# PidiPad.net
KiCad netlist of a schematic drawn in EAGLE
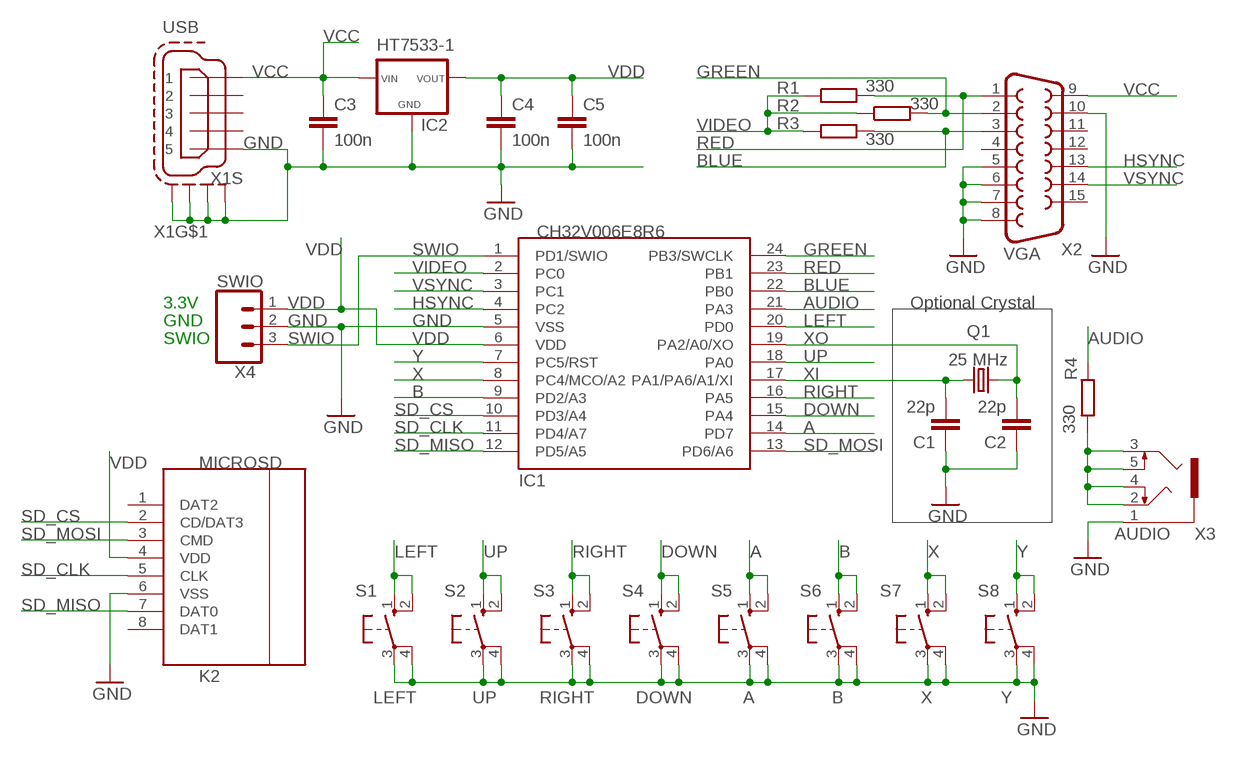
[diagram p0: schematic, sheet 1]

(export (version "E")
  (design (tool "Eeschema 10.0.6"))
  (components
    (comp (ref "C1")
      (value "22p")
      (footprint "eagle-import:C050-024X044")
      (libsource (lib "eagle-import") (part "C-EU050-024X044"))
    )
    (comp (ref "C2")
      (value "22p")
      (footprint "eagle-import:C050-024X044")
      (libsource (lib "eagle-import") (part "C-EU050-024X044"))
    )
    (comp (ref "C3")
      (value "100n")
      (footprint "eagle-import:C050-024X044")
      (libsource (lib "eagle-import") (part "C-EU050-024X044"))
    )
    (comp (ref "C4")
      (value "100n")
      (footprint "eagle-import:C050-024X044")
      (libsource (lib "eagle-import") (part "C-EU050-024X044"))
    )
    (comp (ref "C5")
      (value "100n")
      (footprint "eagle-import:C050-024X044")
      (libsource (lib "eagle-import") (part "C-EU050-024X044"))
    )
    (comp (ref "IC1")
      (value "CH32V006E8R6")
      (footprint "eagle-import:QSOP24")
      (libsource (lib "eagle-import") (part "CH32V006E8R6"))
    )
    (comp (ref "IC2")
      (value "HT7533-1")
      (footprint "eagle-import:HT7533-1")
      (libsource (lib "eagle-import") (part "HT7533-1"))
    )
    (comp (ref "K2")
      (value "MICROSD")
      (footprint "eagle-import:MICROSD")
      (libsource (lib "eagle-import") (part "MICROSD"))
    )
    (comp (ref "Q1")
      (value "25 MHz")
      (footprint "eagle-import:HC49U-V")
      (libsource (lib "eagle-import") (part "CRYSTALHC49U-V"))
    )
    (comp (ref "R1")
      (value "330")
      (footprint "eagle-import:0204_7")
      (libsource (lib "eagle-import") (part "R-EU_0204/7"))
    )
    (comp (ref "R2")
      (value "330")
      (footprint "eagle-import:0204_7")
      (libsource (lib "eagle-import") (part "R-EU_0204/7"))
    )
    (comp (ref "R3")
      (value "330")
      (footprint "eagle-import:0204_7")
      (libsource (lib "eagle-import") (part "R-EU_0204/7"))
    )
    (comp (ref "R4")
      (value "330")
      (footprint "eagle-import:0204_7")
      (libsource (lib "eagle-import") (part "R-EU_0204/7"))
    )
    (comp (ref "S1")
      (value "LEFT")
      (footprint "eagle-import:B3F-10XX")
      (fields (field (name "MPN") "B3F-1000"))
      (libsource (lib "eagle-import") (part "10-XX"))
    )
    (comp (ref "S2")
      (value "UP")
      (footprint "eagle-import:B3F-10XX")
      (fields (field (name "MPN") "B3F-1000"))
      (libsource (lib "eagle-import") (part "10-XX"))
    )
    (comp (ref "S3")
      (value "RIGHT")
      (footprint "eagle-import:B3F-10XX")
      (fields (field (name "MPN") "B3F-1000"))
      (libsource (lib "eagle-import") (part "10-XX"))
    )
    (comp (ref "S4")
      (value "DOWN")
      (footprint "eagle-import:B3F-10XX")
      (fields (field (name "MPN") "B3F-1000"))
      (libsource (lib "eagle-import") (part "10-XX"))
    )
    (comp (ref "S5")
      (value "A")
      (footprint "eagle-import:B3F-10XX")
      (fields (field (name "MPN") "B3F-1000"))
      (libsource (lib "eagle-import") (part "10-XX"))
    )
    (comp (ref "S6")
      (value "B")
      (footprint "eagle-import:B3F-10XX")
      (fields (field (name "MPN") "B3F-1000"))
      (libsource (lib "eagle-import") (part "10-XX"))
    )
    (comp (ref "S7")
      (value "X")
      (footprint "eagle-import:B3F-10XX")
      (fields (field (name "MPN") "B3F-1000"))
      (libsource (lib "eagle-import") (part "10-XX"))
    )
    (comp (ref "S8")
      (value "Y")
      (footprint "eagle-import:B3F-10XX")
      (fields (field (name "MPN") "B3F-1000"))
      (libsource (lib "eagle-import") (part "10-XX"))
    )
    (comp (ref "X1")
      (value "USB")
      (footprint "eagle-import:32005-201")
      (libsource (lib "eagle-import") (part "MINI-USB-SCHIELD-32005-201"))
    )
    (comp (ref "X2")
      (value "VGA")
      (footprint "eagle-import:HDF15H")
      (libsource (lib "eagle-import") (part "F15HDH"))
    )
    (comp (ref "X3")
      (value "AUDIO")
      (footprint "eagle-import:1503_09")
      (libsource (lib "eagle-import") (part "1503_09"))
    )
    (comp (ref "X4")
      (value "SWIO")
      (footprint "eagle-import:1X03")
      (libsource (lib "eagle-import") (part "CONN_03"))
    )
  )
  (nets
    (net (code "1") (name "/A") (class "Default")
      (node (ref "IC1") (pin "14") (pinfunction "PD7_14") (pintype "bidirectional"))
      (node (ref "S5") (pin "1") (pinfunction "S_1") (pintype "passive"))
      (node (ref "S5") (pin "2") (pinfunction "S1_2") (pintype "passive"))
    )
    (net (code "2") (name "/AUDIO") (class "Default")
      (node (ref "IC1") (pin "21") (pinfunction "PA3_21") (pintype "bidirectional"))
      (node (ref "R4") (pin "2") (pinfunction "2_2") (pintype "passive"))
    )
    (net (code "3") (name "/B") (class "Default")
      (node (ref "IC1") (pin "9") (pinfunction "PD2/A3_9") (pintype "bidirectional"))
      (node (ref "S6") (pin "1") (pinfunction "S_1") (pintype "passive"))
      (node (ref "S6") (pin "2") (pinfunction "S1_2") (pintype "passive"))
    )
    (net (code "4") (name "/BLUE") (class "Default")
      (node (ref "IC1") (pin "22") (pinfunction "PB0_22") (pintype "bidirectional"))
      (node (ref "R3") (pin "2") (pinfunction "2_2") (pintype "passive"))
      (node (ref "X2") (pin "3") (pinfunction "3_3") (pintype "passive"))
    )
    (net (code "5") (name "/DOWN") (class "Default")
      (node (ref "IC1") (pin "15") (pinfunction "PA4_15") (pintype "bidirectional"))
      (node (ref "S4") (pin "1") (pinfunction "S_1") (pintype "passive"))
      (node (ref "S4") (pin "2") (pinfunction "S1_2") (pintype "passive"))
    )
    (net (code "6") (name "/GREEN") (class "Default")
      (node (ref "IC1") (pin "24") (pinfunction "PB3/SWCLK_24") (pintype "bidirectional"))
      (node (ref "R2") (pin "2") (pinfunction "2_2") (pintype "passive"))
      (node (ref "X2") (pin "2") (pinfunction "2_2") (pintype "passive"))
    )
    (net (code "7") (name "/HSYNC") (class "Default")
      (node (ref "IC1") (pin "4") (pinfunction "PC2_4") (pintype "bidirectional"))
      (node (ref "X2") (pin "13") (pinfunction "13_13") (pintype "passive"))
    )
    (net (code "8") (name "/LEFT") (class "Default")
      (node (ref "IC1") (pin "20") (pinfunction "PD0_20") (pintype "bidirectional"))
      (node (ref "S1") (pin "1") (pinfunction "S_1") (pintype "passive"))
      (node (ref "S1") (pin "2") (pinfunction "S1_2") (pintype "passive"))
    )
    (net (code "9") (name "/RED") (class "Default")
      (node (ref "IC1") (pin "23") (pinfunction "PB1_23") (pintype "bidirectional"))
      (node (ref "R1") (pin "2") (pinfunction "2_2") (pintype "passive"))
      (node (ref "X2") (pin "1") (pinfunction "1_1") (pintype "passive"))
    )
    (net (code "10") (name "/RIGHT") (class "Default")
      (node (ref "IC1") (pin "16") (pinfunction "PA5_16") (pintype "bidirectional"))
      (node (ref "S3") (pin "1") (pinfunction "S_1") (pintype "passive"))
      (node (ref "S3") (pin "2") (pinfunction "S1_2") (pintype "passive"))
    )
    (net (code "11") (name "/SD_CLK") (class "Default")
      (node (ref "IC1") (pin "11") (pinfunction "PD4/A7_11") (pintype "bidirectional"))
      (node (ref "K2") (pin "5") (pinfunction "CLK_5") (pintype "bidirectional"))
    )
    (net (code "12") (name "/SD_CS") (class "Default")
      (node (ref "IC1") (pin "10") (pinfunction "PD3/A4_10") (pintype "bidirectional"))
      (node (ref "K2") (pin "2") (pinfunction "CD/DAT3_2") (pintype "bidirectional"))
    )
    (net (code "13") (name "/SD_MISO") (class "Default")
      (node (ref "IC1") (pin "12") (pinfunction "PD5/A5_12") (pintype "bidirectional"))
      (node (ref "K2") (pin "7") (pinfunction "DAT0_7") (pintype "bidirectional"))
    )
    (net (code "14") (name "/SD_MOSI") (class "Default")
      (node (ref "IC1") (pin "13") (pinfunction "PD6/A6_13") (pintype "bidirectional"))
      (node (ref "K2") (pin "3") (pinfunction "CMD_3") (pintype "bidirectional"))
    )
    (net (code "15") (name "/SWIO") (class "Default")
      (node (ref "IC1") (pin "1") (pinfunction "PD1/SWIO_1") (pintype "bidirectional"))
      (node (ref "X4") (pin "3") (pinfunction "3_3") (pintype "passive"))
    )
    (net (code "16") (name "/UP") (class "Default")
      (node (ref "IC1") (pin "18") (pinfunction "PA0_18") (pintype "bidirectional"))
      (node (ref "S2") (pin "1") (pinfunction "S_1") (pintype "passive"))
      (node (ref "S2") (pin "2") (pinfunction "S1_2") (pintype "passive"))
    )
    (net (code "17") (name "/VCC") (class "Default")
      (node (ref "C3") (pin "1") (pinfunction "1_1") (pintype "passive"))
      (node (ref "IC2") (pin "VIN") (pinfunction "VIN_VIN") (pintype "input"))
      (node (ref "X1") (pin "1") (pinfunction "1_1") (pintype "passive"))
      (node (ref "X2") (pin "9") (pinfunction "9_9") (pintype "passive"))
    )
    (net (code "18") (name "/VDD") (class "Default")
      (node (ref "C4") (pin "1") (pinfunction "1_1") (pintype "passive"))
      (node (ref "C5") (pin "1") (pinfunction "1_1") (pintype "passive"))
      (node (ref "IC1") (pin "6") (pinfunction "VDD_6") (pintype "power_in"))
      (node (ref "IC2") (pin "VOUT") (pinfunction "VOUT_VOUT") (pintype "passive"))
      (node (ref "K2") (pin "4") (pinfunction "VDD_4") (pintype "bidirectional"))
      (node (ref "X4") (pin "1") (pinfunction "1_1") (pintype "passive"))
    )
    (net (code "19") (name "/VIDEO") (class "Default")
      (node (ref "IC1") (pin "2") (pinfunction "PC0_2") (pintype "bidirectional"))
      (node (ref "R1") (pin "1") (pinfunction "1_1") (pintype "passive"))
      (node (ref "R2") (pin "1") (pinfunction "1_1") (pintype "passive"))
      (node (ref "R3") (pin "1") (pinfunction "1_1") (pintype "passive"))
    )
    (net (code "20") (name "/VSYNC") (class "Default")
      (node (ref "IC1") (pin "3") (pinfunction "PC1_3") (pintype "bidirectional"))
      (node (ref "X2") (pin "14") (pinfunction "14_14") (pintype "passive"))
    )
    (net (code "21") (name "/X") (class "Default")
      (node (ref "IC1") (pin "8") (pinfunction "PC4/MCO/A2_8") (pintype "bidirectional"))
      (node (ref "S7") (pin "1") (pinfunction "S_1") (pintype "passive"))
      (node (ref "S7") (pin "2") (pinfunction "S1_2") (pintype "passive"))
    )
    (net (code "22") (name "/XI") (class "Default")
      (node (ref "C1") (pin "2") (pinfunction "2_2") (pintype "passive"))
      (node (ref "IC1") (pin "17") (pinfunction "PA1/PA6/A1/XI_17") (pintype "bidirectional"))
      (node (ref "Q1") (pin "2") (pinfunction "2_2") (pintype "passive"))
    )
    (net (code "23") (name "/XO") (class "Default")
      (node (ref "C2") (pin "2") (pinfunction "2_2") (pintype "passive"))
      (node (ref "IC1") (pin "19") (pinfunction "PA2/A0/XO_19") (pintype "bidirectional"))
      (node (ref "Q1") (pin "1") (pinfunction "1_1") (pintype "passive"))
    )
    (net (code "24") (name "/Y") (class "Default")
      (node (ref "IC1") (pin "7") (pinfunction "PC5/RST_7") (pintype "bidirectional"))
      (node (ref "S8") (pin "1") (pinfunction "S_1") (pintype "passive"))
      (node (ref "S8") (pin "2") (pinfunction "S1_2") (pintype "passive"))
    )
    (net (code "25") (name "GND") (class "Default")
      (node (ref "C1") (pin "1") (pinfunction "1_1") (pintype "passive"))
      (node (ref "C2") (pin "1") (pinfunction "1_1") (pintype "passive"))
      (node (ref "C3") (pin "2") (pinfunction "2_2") (pintype "passive"))
      (node (ref "C4") (pin "2") (pinfunction "2_2") (pintype "passive"))
      (node (ref "C5") (pin "2") (pinfunction "2_2") (pintype "passive"))
      (node (ref "IC1") (pin "5") (pinfunction "VSS_5") (pintype "power_in"))
      (node (ref "IC2") (pin "GND") (pinfunction "GND_GND") (pintype "input"))
      (node (ref "K2") (pin "6") (pinfunction "VSS_6") (pintype "bidirectional"))
      (node (ref "S1") (pin "3") (pinfunction "P_3") (pintype "passive"))
      (node (ref "S1") (pin "4") (pinfunction "P1_4") (pintype "passive"))
      (node (ref "S2") (pin "3") (pinfunction "P_3") (pintype "passive"))
      (node (ref "S2") (pin "4") (pinfunction "P1_4") (pintype "passive"))
      (node (ref "S3") (pin "3") (pinfunction "P_3") (pintype "passive"))
      (node (ref "S3") (pin "4") (pinfunction "P1_4") (pintype "passive"))
      (node (ref "S4") (pin "3") (pinfunction "P_3") (pintype "passive"))
      (node (ref "S4") (pin "4") (pinfunction "P1_4") (pintype "passive"))
      (node (ref "S5") (pin "3") (pinfunction "P_3") (pintype "passive"))
      (node (ref "S5") (pin "4") (pinfunction "P1_4") (pintype "passive"))
      (node (ref "S6") (pin "3") (pinfunction "P_3") (pintype "passive"))
      (node (ref "S6") (pin "4") (pinfunction "P1_4") (pintype "passive"))
      (node (ref "S7") (pin "3") (pinfunction "P_3") (pintype "passive"))
      (node (ref "S7") (pin "4") (pinfunction "P1_4") (pintype "passive"))
      (node (ref "S8") (pin "3") (pinfunction "P_3") (pintype "passive"))
      (node (ref "S8") (pin "4") (pinfunction "P1_4") (pintype "passive"))
      (node (ref "X1") (pin "5") (pinfunction "5_5") (pintype "passive"))
      (node (ref "X1") (pin "M1") (pinfunction "S1_M1") (pintype "passive"))
      (node (ref "X1") (pin "M2") (pinfunction "S2_M2") (pintype "passive"))
      (node (ref "X1") (pin "M3") (pinfunction "S3_M3") (pintype "passive"))
      (node (ref "X1") (pin "M4") (pinfunction "S4_M4") (pintype "passive"))
      (node (ref "X2") (pin "10") (pinfunction "10_10") (pintype "passive"))
      (node (ref "X2") (pin "5") (pinfunction "5_5") (pintype "passive"))
      (node (ref "X2") (pin "6") (pinfunction "6_6") (pintype "passive"))
      (node (ref "X2") (pin "7") (pinfunction "7_7") (pintype "passive"))
      (node (ref "X2") (pin "8") (pinfunction "8_8") (pintype "passive"))
      (node (ref "X3") (pin "1") (pinfunction "1_1") (pintype "passive"))
      (node (ref "X4") (pin "2") (pinfunction "2_2") (pintype "passive"))
    )
    (net (code "26") (name "Net-(R4-Pad1)") (class "Default")
      (node (ref "R4") (pin "1") (pinfunction "1_1") (pintype "passive"))
      (node (ref "X3") (pin "2") (pinfunction "2_2") (pintype "passive"))
      (node (ref "X3") (pin "3") (pinfunction "3_3") (pintype "passive"))
      (node (ref "X3") (pin "4") (pinfunction "4_4") (pintype "passive"))
      (node (ref "X3") (pin "5") (pinfunction "5_5") (pintype "passive"))
    )
    (net (code "27") (name "unconnected-(K2-DAT1-Pad8)") (class "Default")
      (node (ref "K2") (pin "8") (pinfunction "DAT1_8") (pintype "bidirectional"))
    )
    (net (code "28") (name "unconnected-(K2-DAT2-Pad1)") (class "Default")
      (node (ref "K2") (pin "1") (pinfunction "DAT2_1") (pintype "bidirectional"))
    )
    (net (code "29") (name "unconnected-(X1-Pad2)") (class "Default")
      (node (ref "X1") (pin "2") (pinfunction "2_2") (pintype "passive"))
    )
    (net (code "30") (name "unconnected-(X1-Pad3)") (class "Default")
      (node (ref "X1") (pin "3") (pinfunction "3_3") (pintype "passive"))
    )
    (net (code "31") (name "unconnected-(X1-Pad4)") (class "Default")
      (node (ref "X1") (pin "4") (pinfunction "4_4") (pintype "passive"))
    )
    (net (code "32") (name "unconnected-(X2-Pad4)") (class "Default")
      (node (ref "X2") (pin "4") (pinfunction "4_4") (pintype "passive"))
    )
    (net (code "33") (name "unconnected-(X2-Pad11)") (class "Default")
      (node (ref "X2") (pin "11") (pinfunction "11_11") (pintype "passive"))
    )
    (net (code "34") (name "unconnected-(X2-Pad12)") (class "Default")
      (node (ref "X2") (pin "12") (pinfunction "12_12") (pintype "passive"))
    )
    (net (code "35") (name "unconnected-(X2-Pad15)") (class "Default")
      (node (ref "X2") (pin "15") (pinfunction "15_15") (pintype "passive"))
    )
  )
)
